# 2002_Pile-Accu.net
KiCad netlist of a schematic drawn in Altium Designer
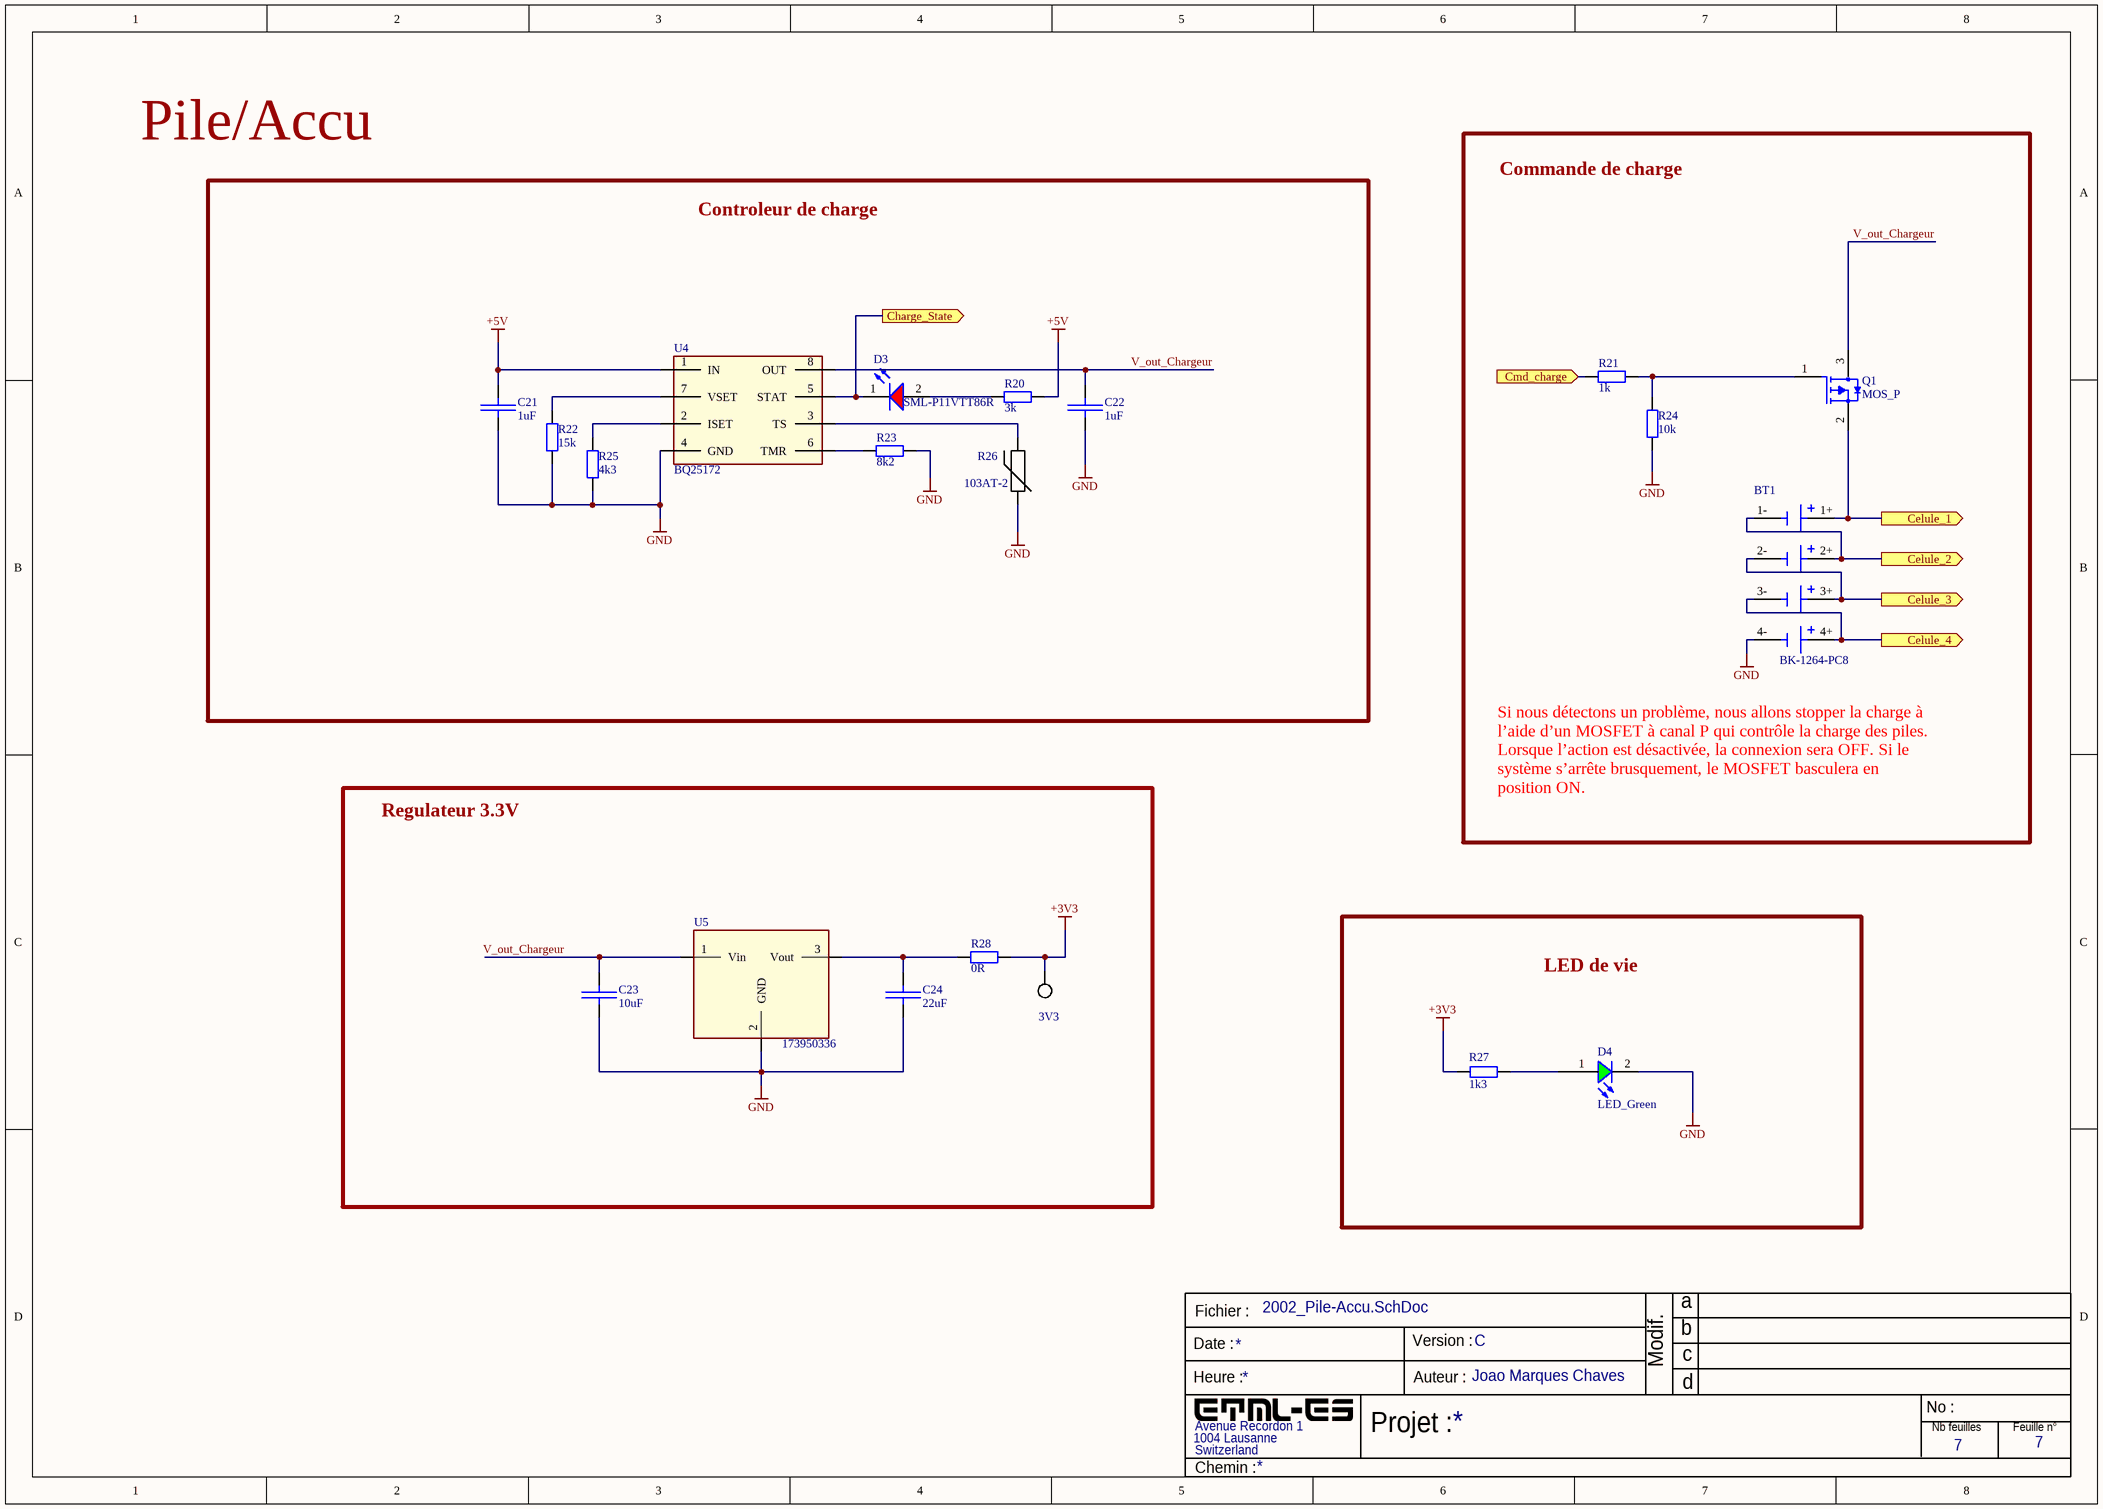
[diagram p0: 2002_Pile-Accu.SchDoc]

(export (version "E")
  (design (tool "Eeschema 10.0.6"))
  (components
    (comp (ref "3V3")
      (value "5019")
      (footprint "TESTPOINT_SMD")
      (description "Test point smd")
      (libsource (lib "2002_CapteurMeteoWifi") (part "TESTPOINT"))
    )
    (comp (ref "BT1")
      (value "BK-1264-PC8")
      (footprint "BAT_BK-1264-PC8")
      (description "Battery Holder (Open) AAA 4 Cell PC Pin")
      (libsource (lib "Schlib1") (part "BK-1264-PC8"))
    )
    (comp (ref "C21")
      (value "1uF")
      (footprint "0805")
      (description "Capacitor smd")
      (libsource (lib "2002_CapteurMeteoWifi") (part "Condensator"))
    )
    (comp (ref "C22")
      (value "1uF")
      (footprint "0805")
      (description "Capacitor smd")
      (libsource (lib "2002_CapteurMeteoWifi") (part "Condensator"))
    )
    (comp (ref "C23")
      (value "10uF")
      (footprint "0805")
      (description "Capacitor smd")
      (libsource (lib "2002_CapteurMeteoWifi") (part "Condensator"))
    )
    (comp (ref "C24")
      (value "22uF")
      (footprint "0805")
      (description "Capacitor smd")
      (libsource (lib "2002_CapteurMeteoWifi") (part "Condensator"))
    )
    (comp (ref "D3")
      (value "SML-P11VTT86R")
      (footprint "LED_SML-P11VTT86R")
      (description "WL-SMCW Mono-color Chip LED Waterclear, size 0805, Super Red, 1.9V, 140°")
      (fields
        (field (name "MANUFACTURER PART NUMBER") "150080SS75000")
        (field (name "MANUFACTURER") "Wurth Elektronik")
      )
      (libsource (lib "WL-SMCW") (part "150080SS75000"))
    )
    (comp (ref "D4")
      (value "LED_Green")
      (footprint "LED_SML-P11VTT86R")
      (libsource (lib "Schlib1") (part "LED_Green"))
    )
    (comp (ref "Q1") (value "MOS_P") (footprint "SI5618-TP") (libsource (lib "Schlib1") (part "MOS_P")))
    (comp (ref "R20")
      (value "3k")
      (footprint "0805")
      (description "Resistor smd")
      (fields (field (name "Comment") "3k2") (field (name "PUBLISHER") "Altium Limited"))
      (libsource (lib "2209_CommandeDomotiqueIR_1") (part "Res2_1"))
    )
    (comp (ref "R21")
      (value "1k")
      (footprint "0805")
      (description "Resistor smd")
      (fields (field (name "PUBLISHER") "Altium Limited"))
      (libsource (lib "2209_CommandeDomotiqueIR_1") (part "Res2"))
    )
    (comp (ref "R22")
      (value "15k")
      (footprint "0805")
      (description "Resistor smd")
      (fields (field (name "PUBLISHER") "Altium Limited"))
      (libsource (lib "") (part "Res2_1_1"))
    )
    (comp (ref "R23")
      (value "8k2")
      (footprint "0805")
      (description "Resistor smd")
      (fields (field (name "PUBLISHER") "Altium Limited"))
      (libsource (lib "2209_CommandeDomotiqueIR_1") (part "Res2_1"))
    )
    (comp (ref "R24")
      (value "10k")
      (footprint "0805")
      (description "Resistor smd")
      (fields (field (name "PUBLISHER") "Altium Limited"))
      (libsource (lib "") (part "Res2_1_1"))
    )
    (comp (ref "R25")
      (value "4k3")
      (footprint "0805")
      (description "Resistor smd")
      (fields (field (name "PUBLISHER") "Altium Limited"))
      (libsource (lib "") (part "Res2_1_1"))
    )
    (comp (ref "R26")
      (value "103AT-2")
      (footprint "103AT51PFT")
      (description "thermistor")
      (libsource (lib "Schlib1") (part "103AT-2"))
    )
    (comp (ref "R27")
      (value "1k3")
      (footprint "0805")
      (description "SMD Resistor")
      (fields (field (name "RESISTANCE") "1k3"))
      (libsource (lib "2312-MS-0805") (part "RES-0805"))
    )
    (comp (ref "R28")
      (value "0R")
      (footprint "0805")
      (description "Resistor smd")
      (fields (field (name "PUBLISHER") "Altium Limited"))
      (libsource (lib "2209_CommandeDomotiqueIR_1") (part "Res2_1"))
    )
    (comp (ref "U4")
      (value "BQ25172")
      (footprint "BQ25172DSGR")
      (description "Linear Battery Charger for 1- to 6-Cell NiMH Batteries")
      (libsource (lib "Schlib1") (part "BQ25172"))
    )
    (comp (ref "U5")
      (value "173950336")
      (footprint "173950336")
      (description "DC DC CONVERTER 3.3V")
      (libsource (lib "Schlib1") (part "173950336"))
    )
  )
  (nets
    (net (code "1") (name "+3V3") (class "Default")
      (node (ref "3V3") (pin "1") (pinfunction "1_1") (pintype "passive"))
      (node (ref "R27") (pin "1") (pinfunction "1_1") (pintype "passive"))
      (node (ref "R28") (pin "1") (pinfunction "1_1") (pintype "passive"))
    )
    (net (code "2") (name "+5V") (class "Default")
      (node (ref "C21") (pin "1") (pinfunction "1_1") (pintype "passive"))
      (node (ref "R20") (pin "1") (pinfunction "1_1") (pintype "passive"))
      (node (ref "U4") (pin "1") (pinfunction "IN_1") (pintype "passive"))
    )
    (net (code "3") (name "/Celule_1") (class "Default")
      (node (ref "BT1") (pin "1+") (pinfunction "1+_1+") (pintype "passive"))
      (node (ref "Q1") (pin "2") (pinfunction "S_2") (pintype "passive"))
    )
    (net (code "4") (name "/Celule_2") (class "Default")
      (node (ref "BT1") (pin "1-") (pinfunction "1-_1-") (pintype "passive"))
      (node (ref "BT1") (pin "2+") (pinfunction "2+_2+") (pintype "passive"))
    )
    (net (code "5") (name "/Celule_3") (class "Default")
      (node (ref "BT1") (pin "2-") (pinfunction "2-_2-") (pintype "passive"))
      (node (ref "BT1") (pin "3+") (pinfunction "3+_3+") (pintype "passive"))
    )
    (net (code "6") (name "/Celule_4") (class "Default")
      (node (ref "BT1") (pin "3-") (pinfunction "3-_3-") (pintype "passive"))
      (node (ref "BT1") (pin "4+") (pinfunction "4+_4+") (pintype "passive"))
    )
    (net (code "7") (name "/Charge_State") (class "Default")
      (node (ref "D3") (pin "1") (pinfunction "K_1") (pintype "passive"))
      (node (ref "U4") (pin "5") (pinfunction "STAT_5") (pintype "passive"))
    )
    (net (code "8") (name "/Cmd_charge") (class "Default")
      (node (ref "R21") (pin "2") (pinfunction "2_2") (pintype "passive"))
    )
    (net (code "9") (name "/V_out_Chargeur") (class "Default")
      (node (ref "C22") (pin "1") (pinfunction "1_1") (pintype "passive"))
      (node (ref "C23") (pin "1") (pinfunction "1_1") (pintype "passive"))
      (node (ref "Q1") (pin "3") (pinfunction "D_3") (pintype "passive"))
      (node (ref "U4") (pin "8") (pinfunction "OUT_8") (pintype "passive"))
      (node (ref "U5") (pin "1") (pinfunction "Vin_1") (pintype "passive"))
    )
    (net (code "10") (name "GND") (class "Default")
      (node (ref "BT1") (pin "4-") (pinfunction "4-_4-") (pintype "passive"))
      (node (ref "C21") (pin "2") (pinfunction "2_2") (pintype "passive"))
      (node (ref "C22") (pin "2") (pinfunction "2_2") (pintype "passive"))
      (node (ref "C23") (pin "2") (pinfunction "2_2") (pintype "passive"))
      (node (ref "C24") (pin "2") (pinfunction "2_2") (pintype "passive"))
      (node (ref "D4") (pin "2") (pintype "passive"))
      (node (ref "R22") (pin "1") (pinfunction "1_1") (pintype "passive"))
      (node (ref "R23") (pin "1") (pinfunction "1_1") (pintype "passive"))
      (node (ref "R24") (pin "1") (pinfunction "1_1") (pintype "passive"))
      (node (ref "R25") (pin "1") (pinfunction "1_1") (pintype "passive"))
      (node (ref "R26") (pin "2") (pinfunction "0_2") (pintype "passive"))
      (node (ref "U4") (pin "4") (pinfunction "GND_4") (pintype "passive"))
      (node (ref "U5") (pin "2") (pinfunction "GND_2") (pintype "passive"))
    )
    (net (code "11") (name "Net-(D3-A)") (class "Default")
      (node (ref "D3") (pin "2") (pinfunction "A_2") (pintype "passive"))
      (node (ref "R20") (pin "2") (pinfunction "2_2") (pintype "passive"))
    )
    (net (code "12") (name "Net-(D4-0)") (class "Default")
      (node (ref "D4") (pin "1") (pinfunction "0_1") (pintype "passive"))
      (node (ref "R27") (pin "2") (pinfunction "2_2") (pintype "passive"))
    )
    (net (code "13") (name "Net-(Q1-G)") (class "Default")
      (node (ref "Q1") (pin "1") (pinfunction "G_1") (pintype "passive"))
      (node (ref "R21") (pin "1") (pinfunction "1_1") (pintype "passive"))
      (node (ref "R24") (pin "2") (pinfunction "2_2") (pintype "passive"))
    )
    (net (code "14") (name "Net-(U4-ISET)") (class "Default")
      (node (ref "R25") (pin "2") (pinfunction "2_2") (pintype "passive"))
      (node (ref "U4") (pin "2") (pinfunction "ISET_2") (pintype "passive"))
    )
    (net (code "15") (name "Net-(U4-TMR)") (class "Default")
      (node (ref "R23") (pin "2") (pinfunction "2_2") (pintype "passive"))
      (node (ref "U4") (pin "6") (pinfunction "TMR_6") (pintype "passive"))
    )
    (net (code "16") (name "Net-(U4-TS)") (class "Default")
      (node (ref "R26") (pin "1") (pinfunction "0_1") (pintype "passive"))
      (node (ref "U4") (pin "3") (pinfunction "TS_3") (pintype "passive"))
    )
    (net (code "17") (name "Net-(U4-VSET)") (class "Default")
      (node (ref "R22") (pin "2") (pinfunction "2_2") (pintype "passive"))
      (node (ref "U4") (pin "7") (pinfunction "VSET_7") (pintype "passive"))
    )
    (net (code "18") (name "Net-(U5-Vout)") (class "Default")
      (node (ref "C24") (pin "1") (pinfunction "1_1") (pintype "passive"))
      (node (ref "R28") (pin "2") (pinfunction "2_2") (pintype "passive"))
      (node (ref "U5") (pin "3") (pinfunction "Vout_3") (pintype "passive"))
    )
  )
)
